# Power.net
KiCad netlist of a schematic drawn in Altium Designer
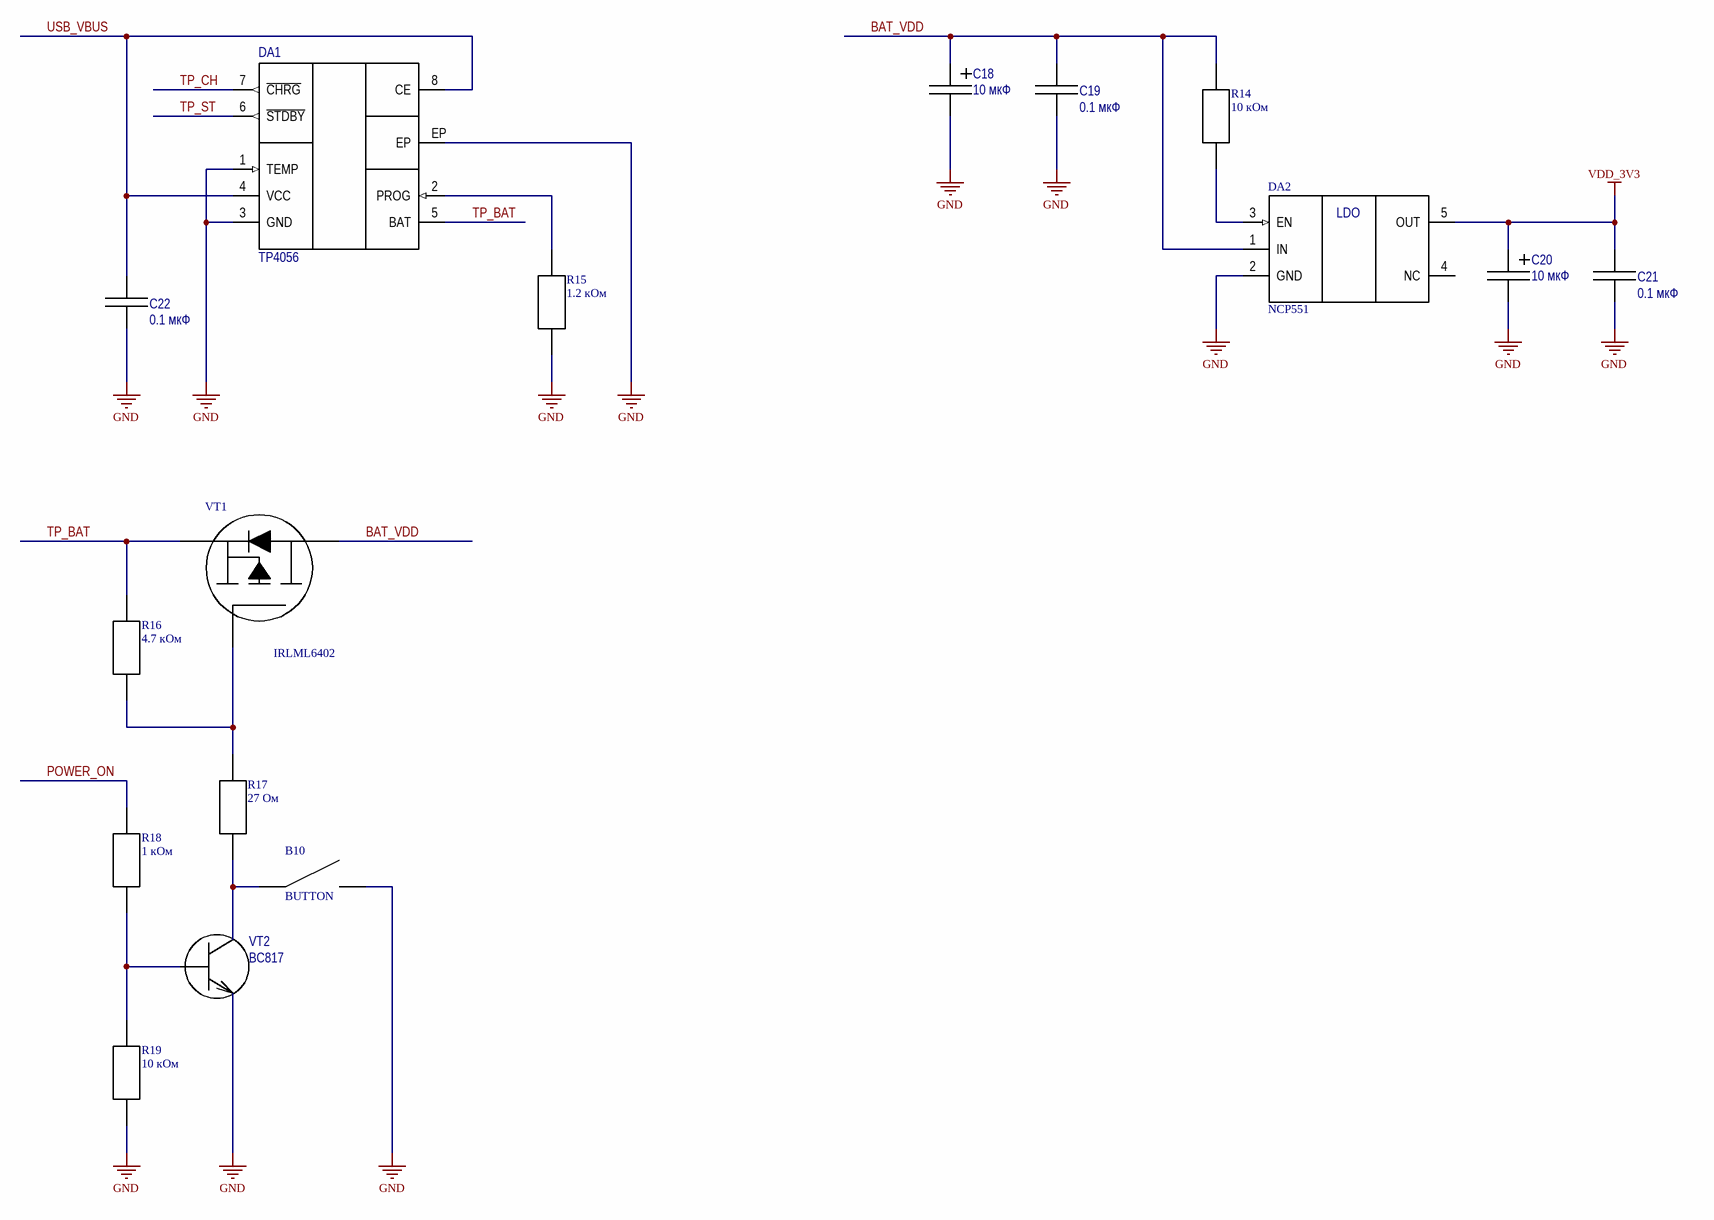
[diagram p0: Power.SchDoc]

(export (version "E")
  (design (tool "Eeschema 10.0.6"))
  (components
    (comp (ref "B10")
      (value "BUTTON")
      (footprint "TACT SKHH Horizontal Switch")
      (libsource (lib "my_lib") (part "BUTTON"))
    )
    (comp (ref "C18")
      (value "10 мкФ")
      (footprint "C TAN_A")
      (description "SMD Tantalium Capacitor A")
      (libsource (lib "my_lib") (part "CAP TAN_A"))
    )
    (comp (ref "C19")
      (value "0.1 мкФ")
      (footprint "C 0805")
      (description "SMD Capacitor 0805")
      (libsource (lib "my_lib") (part "CAP 0805"))
    )
    (comp (ref "C20")
      (value "10 мкФ")
      (footprint "C TAN_A")
      (description "SMD Tantalium Capacitor A")
      (libsource (lib "my_lib") (part "CAP TAN_A"))
    )
    (comp (ref "C21")
      (value "0.1 мкФ")
      (footprint "C 0805")
      (description "SMD Capacitor 0805")
      (libsource (lib "my_lib") (part "CAP 0805"))
    )
    (comp (ref "C22")
      (value "0.1 мкФ")
      (footprint "C 0805")
      (description "SMD Capacitor 0805")
      (libsource (lib "my_lib") (part "CAP 0805"))
    )
    (comp (ref "DA1") (value "TP4056") (footprint "HSOP-8") (libsource (lib "my_lib") (part "TP4056")))
    (comp (ref "DA2") (value "NCP551") (footprint "TSOP-5") (libsource (lib "my_lib") (part "NCP551")))
    (comp (ref "R14") (value "10 кОм") (footprint "RES 0402") (libsource (lib "my_lib") (part "RES 0402")))
    (comp (ref "R15") (value "1.2 кОм") (footprint "RES 0402") (libsource (lib "my_lib") (part "RES 0402")))
    (comp (ref "R16") (value "4.7 кОм") (footprint "RES 0402") (libsource (lib "my_lib") (part "RES 0402")))
    (comp (ref "R17") (value "27 Ом") (footprint "RES 0402") (libsource (lib "my_lib") (part "RES 0402")))
    (comp (ref "R18") (value "1 кОм") (footprint "RES 0402") (libsource (lib "my_lib") (part "RES 0402")))
    (comp (ref "R19") (value "10 кОм") (footprint "RES 0402") (libsource (lib "my_lib") (part "RES 0402")))
    (comp (ref "VT1") (value "IRLML6402") (footprint "SOT-23") (libsource (lib "my_lib") (part "IRLML6402")))
    (comp (ref "VT2")
      (value "BC817")
      (footprint "SOT-23")
      (description "NPN general-purpose transistor")
      (fields (field (name "MANUFACTURER") "NXP"))
      (libsource (lib "my_lib") (part "BC817"))
    )
  )
  (nets
    (net (code "1") (name "/BAT_VDD") (class "Default")
      (node (ref "C18") (pin "1") (pinfunction "1_1") (pintype "passive"))
      (node (ref "C19") (pin "2") (pinfunction "2_2") (pintype "passive"))
      (node (ref "DA2") (pin "1") (pinfunction "IN_1") (pintype "passive"))
      (node (ref "R14") (pin "2") (pinfunction "2_2") (pintype "passive"))
      (node (ref "VT1") (pin "3") (pinfunction "D_3") (pintype "passive"))
    )
    (net (code "2") (name "/POWER_ON") (class "Default")
      (node (ref "R18") (pin "2") (pinfunction "2_2") (pintype "passive"))
    )
    (net (code "3") (name "/TP_BAT") (class "Default")
      (node (ref "DA1") (pin "5") (pinfunction "BAT_5") (pintype "power_in"))
      (node (ref "R16") (pin "2") (pinfunction "2_2") (pintype "passive"))
      (node (ref "VT1") (pin "2") (pinfunction "S_2") (pintype "passive"))
    )
    (net (code "4") (name "/TP_CH") (class "Default")
      (node (ref "DA1") (pin "7") (pinfunction "~{CHRG}_7") (pintype "output"))
    )
    (net (code "5") (name "/TP_ST") (class "Default")
      (node (ref "DA1") (pin "6") (pinfunction "~{STDBY}_6") (pintype "output"))
    )
    (net (code "6") (name "/USB_VBUS") (class "Default")
      (node (ref "C22") (pin "2") (pinfunction "2_2") (pintype "passive"))
      (node (ref "DA1") (pin "4") (pinfunction "VCC_4") (pintype "power_in"))
      (node (ref "DA1") (pin "8") (pinfunction "CE_8") (pintype "passive"))
    )
    (net (code "7") (name "GND") (class "Default")
      (node (ref "B10") (pin "2") (pinfunction "2_2") (pintype "passive"))
      (node (ref "C18") (pin "2") (pinfunction "2_2") (pintype "passive"))
      (node (ref "C19") (pin "1") (pinfunction "1_1") (pintype "passive"))
      (node (ref "C20") (pin "2") (pinfunction "2_2") (pintype "passive"))
      (node (ref "C21") (pin "1") (pinfunction "1_1") (pintype "passive"))
      (node (ref "C22") (pin "1") (pinfunction "1_1") (pintype "passive"))
      (node (ref "DA1") (pin "1") (pinfunction "TEMP_1") (pintype "input"))
      (node (ref "DA1") (pin "3") (pinfunction "GND_3") (pintype "power_in"))
      (node (ref "DA1") (pin "EP") (pinfunction "EP_EP") (pintype "passive"))
      (node (ref "DA2") (pin "2") (pinfunction "GND_2") (pintype "passive"))
      (node (ref "R15") (pin "1") (pinfunction "1_1") (pintype "passive"))
      (node (ref "R19") (pin "1") (pinfunction "1_1") (pintype "passive"))
      (node (ref "VT2") (pin "2") (pinfunction "E_2") (pintype "passive"))
    )
    (net (code "8") (name "Net-(DA1-PROG)") (class "Default")
      (node (ref "DA1") (pin "2") (pinfunction "PROG_2") (pintype "input"))
      (node (ref "R15") (pin "2") (pinfunction "2_2") (pintype "passive"))
    )
    (net (code "9") (name "Net-(DA2-EN)") (class "Default")
      (node (ref "DA2") (pin "3") (pinfunction "EN_3") (pintype "input"))
      (node (ref "R14") (pin "1") (pinfunction "1_1") (pintype "passive"))
    )
    (net (code "10") (name "Net-(VT1-G)") (class "Default")
      (node (ref "R16") (pin "1") (pinfunction "1_1") (pintype "passive"))
      (node (ref "R17") (pin "2") (pinfunction "2_2") (pintype "passive"))
      (node (ref "VT1") (pin "1") (pinfunction "G_1") (pintype "passive"))
    )
    (net (code "11") (name "Net-(VT2-B)") (class "Default")
      (node (ref "R18") (pin "1") (pinfunction "1_1") (pintype "passive"))
      (node (ref "R19") (pin "2") (pinfunction "2_2") (pintype "passive"))
      (node (ref "VT2") (pin "1") (pinfunction "B_1") (pintype "passive"))
    )
    (net (code "12") (name "Net-(VT2-C)") (class "Default")
      (node (ref "B10") (pin "1") (pinfunction "1_1") (pintype "passive"))
      (node (ref "R17") (pin "1") (pinfunction "1_1") (pintype "passive"))
      (node (ref "VT2") (pin "3") (pinfunction "C_3") (pintype "passive"))
    )
    (net (code "13") (name "VDD_3V3") (class "Default")
      (node (ref "C20") (pin "1") (pinfunction "1_1") (pintype "passive"))
      (node (ref "C21") (pin "2") (pinfunction "2_2") (pintype "passive"))
      (node (ref "DA2") (pin "5") (pinfunction "OUT_5") (pintype "passive"))
    )
    (net (code "14") (name "unconnected-(DA2-NC-Pad4)") (class "Default")
      (node (ref "DA2") (pin "4") (pinfunction "NC_4") (pintype "passive"))
    )
  )
)
